# Sheet1.net
KiCad netlist of a schematic drawn in Altium Designer
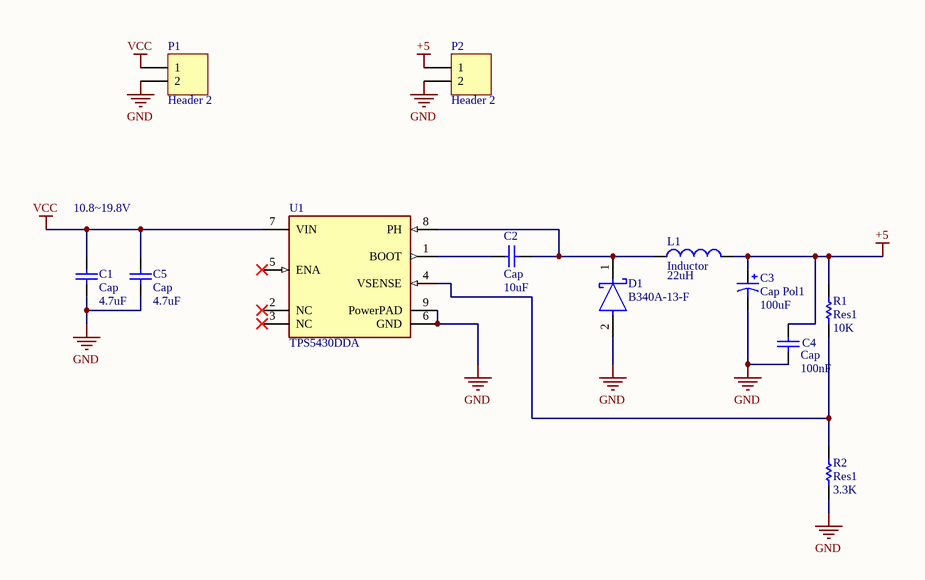
[diagram p0: Sheet1.SchDoc]

(export (version "E")
  (design (tool "Eeschema 10.0.6"))
  (components
    (comp (ref "C1")
      (value "Cap")
      (footprint "RAD-0.3")
      (description "Capacitor")
      (fields (field (name "ALTIUM_VALUE") "4.7uF") (field (name "PUBLISHER") "Altium Limited"))
      (libsource (lib "Miscellaneous Devices") (part "Cap"))
    )
    (comp (ref "C2")
      (value "Cap")
      (footprint "RAD-0.3")
      (description "Capacitor")
      (fields (field (name "ALTIUM_VALUE") "10uF") (field (name "PUBLISHER") "Altium Limited"))
      (libsource (lib "Miscellaneous Devices") (part "Cap"))
    )
    (comp (ref "C3")
      (value "Cap Pol1")
      (footprint "RB7.6-15")
      (description "Polarized Capacitor (Radial)")
      (fields (field (name "ALTIUM_VALUE") "100uF") (field (name "PUBLISHER") "Altium Limited"))
      (libsource (lib "Miscellaneous Devices") (part "Cap Pol1"))
    )
    (comp (ref "C4")
      (value "Cap")
      (footprint "RAD-0.3")
      (description "Capacitor")
      (fields (field (name "ALTIUM_VALUE") "100nF") (field (name "PUBLISHER") "Altium Limited"))
      (libsource (lib "Miscellaneous Devices") (part "Cap"))
    )
    (comp (ref "C5")
      (value "Cap")
      (footprint "RAD-0.3")
      (description "Capacitor")
      (fields (field (name "ALTIUM_VALUE") "4.7uF") (field (name "PUBLISHER") "Altium Limited"))
      (libsource (lib "Miscellaneous Devices") (part "Cap"))
    )
    (comp (ref "D1")
      (value "B340A-13-F")
      (footprint "FP-SMA-MFG")
      (description "DIODE SCHOTTKY 40V 3A SMA")
      (fields (field (name "VOLTAGE") "40V"))
      (libsource (lib "Altium Content Vault") (part "1d6ec82d83fb6aee721767c19dac4b9"))
    )
    (comp (ref "L1")
      (value "Inductor")
      (footprint "0402-A")
      (fields (field (name "ALTIUM_VALUE") "22uH") (field (name "PUBLISHER") "Altium Limited"))
      (libsource (lib "Miscellaneous Devices") (part "Inductor"))
    )
    (comp (ref "P1")
      (value "Header 2")
      (footprint "HDR1X2")
      (description "Header, 2-Pin")
      (fields (field (name "PUBLISHER") "Altium Limited"))
      (libsource (lib "Miscellaneous Connectors") (part "Header 2"))
    )
    (comp (ref "P2")
      (value "Header 2")
      (footprint "HDR1X2")
      (description "Header, 2-Pin")
      (fields (field (name "PUBLISHER") "Altium Limited"))
      (libsource (lib "Miscellaneous Connectors") (part "Header 2"))
    )
    (comp (ref "R1")
      (value "Res1")
      (footprint "AXIAL-0.3")
      (description "Resistor")
      (fields (field (name "ALTIUM_VALUE") "10K") (field (name "PUBLISHER") "Altium Limited"))
      (libsource (lib "Miscellaneous Devices") (part "Res1"))
    )
    (comp (ref "R2")
      (value "Res1")
      (footprint "AXIAL-0.3")
      (description "Resistor")
      (fields (field (name "ALTIUM_VALUE") "3.3K") (field (name "PUBLISHER") "Altium Limited"))
      (libsource (lib "Miscellaneous Devices") (part "Res1"))
    )
    (comp (ref "U1")
      (value "TPS5430DDA")
      (footprint "FP-DDA0008J-MFG")
      (description "IC REG BUCK ADJUSTABLE 3A 8SOPWR")
      (fields
        (field (name "MANUFACTURER") "Texas Instruments")
        (field (name "OCTOPART") "https://octopart.com/tps5430dda-texas+instruments-589977")
      )
      (libsource (lib "Altium Content Vault") (part "98da629940cea6febc5630bb55159f3"))
    )
  )
  (nets
    (net (code "1") (name "+5") (class "Default")
      (node (ref "C3") (pin "1") (pinfunction "1_1") (pintype "passive"))
      (node (ref "C4") (pin "2") (pinfunction "2_2") (pintype "passive"))
      (node (ref "L1") (pin "2") (pinfunction "2_2") (pintype "passive"))
      (node (ref "P2") (pin "1") (pinfunction "1_1") (pintype "passive"))
      (node (ref "R1") (pin "2") (pinfunction "2_2") (pintype "passive"))
    )
    (net (code "2") (name "GND") (class "Default")
      (node (ref "C1") (pin "1") (pinfunction "1_1") (pintype "passive"))
      (node (ref "C3") (pin "2") (pinfunction "2_2") (pintype "passive"))
      (node (ref "C4") (pin "1") (pinfunction "1_1") (pintype "passive"))
      (node (ref "C5") (pin "1") (pinfunction "1_1") (pintype "passive"))
      (node (ref "D1") (pin "2") (pinfunction "A_2") (pintype "passive"))
      (node (ref "P1") (pin "2") (pinfunction "2_2") (pintype "passive"))
      (node (ref "P2") (pin "2") (pinfunction "2_2") (pintype "passive"))
      (node (ref "R2") (pin "1") (pinfunction "1_1") (pintype "passive"))
      (node (ref "U1") (pin "6") (pinfunction "GND_6") (pintype "power_in"))
      (node (ref "U1") (pin "9") (pinfunction "PowerPAD_9") (pintype "power_in"))
    )
    (net (code "3") (name "Net-(D1-C)") (class "Default")
      (node (ref "C2") (pin "1") (pinfunction "1_1") (pintype "passive"))
      (node (ref "D1") (pin "1") (pinfunction "C_1") (pintype "passive"))
      (node (ref "L1") (pin "1") (pinfunction "1_1") (pintype "passive"))
      (node (ref "U1") (pin "8") (pinfunction "PH_8") (pintype "input"))
    )
    (net (code "4") (name "Net-(U1-BOOT)") (class "Default")
      (node (ref "C2") (pin "2") (pinfunction "2_2") (pintype "passive"))
      (node (ref "U1") (pin "1") (pinfunction "BOOT_1") (pintype "output"))
    )
    (net (code "5") (name "Net-(U1-VSENSE)") (class "Default")
      (node (ref "R1") (pin "1") (pinfunction "1_1") (pintype "passive"))
      (node (ref "R2") (pin "2") (pinfunction "2_2") (pintype "passive"))
      (node (ref "U1") (pin "4") (pinfunction "VSENSE_4") (pintype "input"))
    )
    (net (code "6") (name "VCC") (class "Default")
      (node (ref "C1") (pin "2") (pinfunction "2_2") (pintype "passive"))
      (node (ref "C5") (pin "2") (pinfunction "2_2") (pintype "passive"))
      (node (ref "P1") (pin "1") (pinfunction "1_1") (pintype "passive"))
      (node (ref "U1") (pin "7") (pinfunction "VIN_7") (pintype "power_in"))
    )
    (net (code "7") (name "unconnected-(U1-ENA-Pad5)") (class "Default")
      (node (ref "U1") (pin "5") (pinfunction "ENA_5") (pintype "input+no_connect"))
    )
    (net (code "8") (name "unconnected-(U1-NC-Pad2)") (class "Default")
      (node (ref "U1") (pin "2") (pinfunction "NC_2") (pintype "passive+no_connect"))
    )
    (net (code "9") (name "unconnected-(U1-NC-Pad3)") (class "Default")
      (node (ref "U1") (pin "3") (pinfunction "NC_3") (pintype "passive+no_connect"))
    )
  )
)
